# Hardware_Schematic.net
KiCad netlist of a schematic drawn in EAGLE
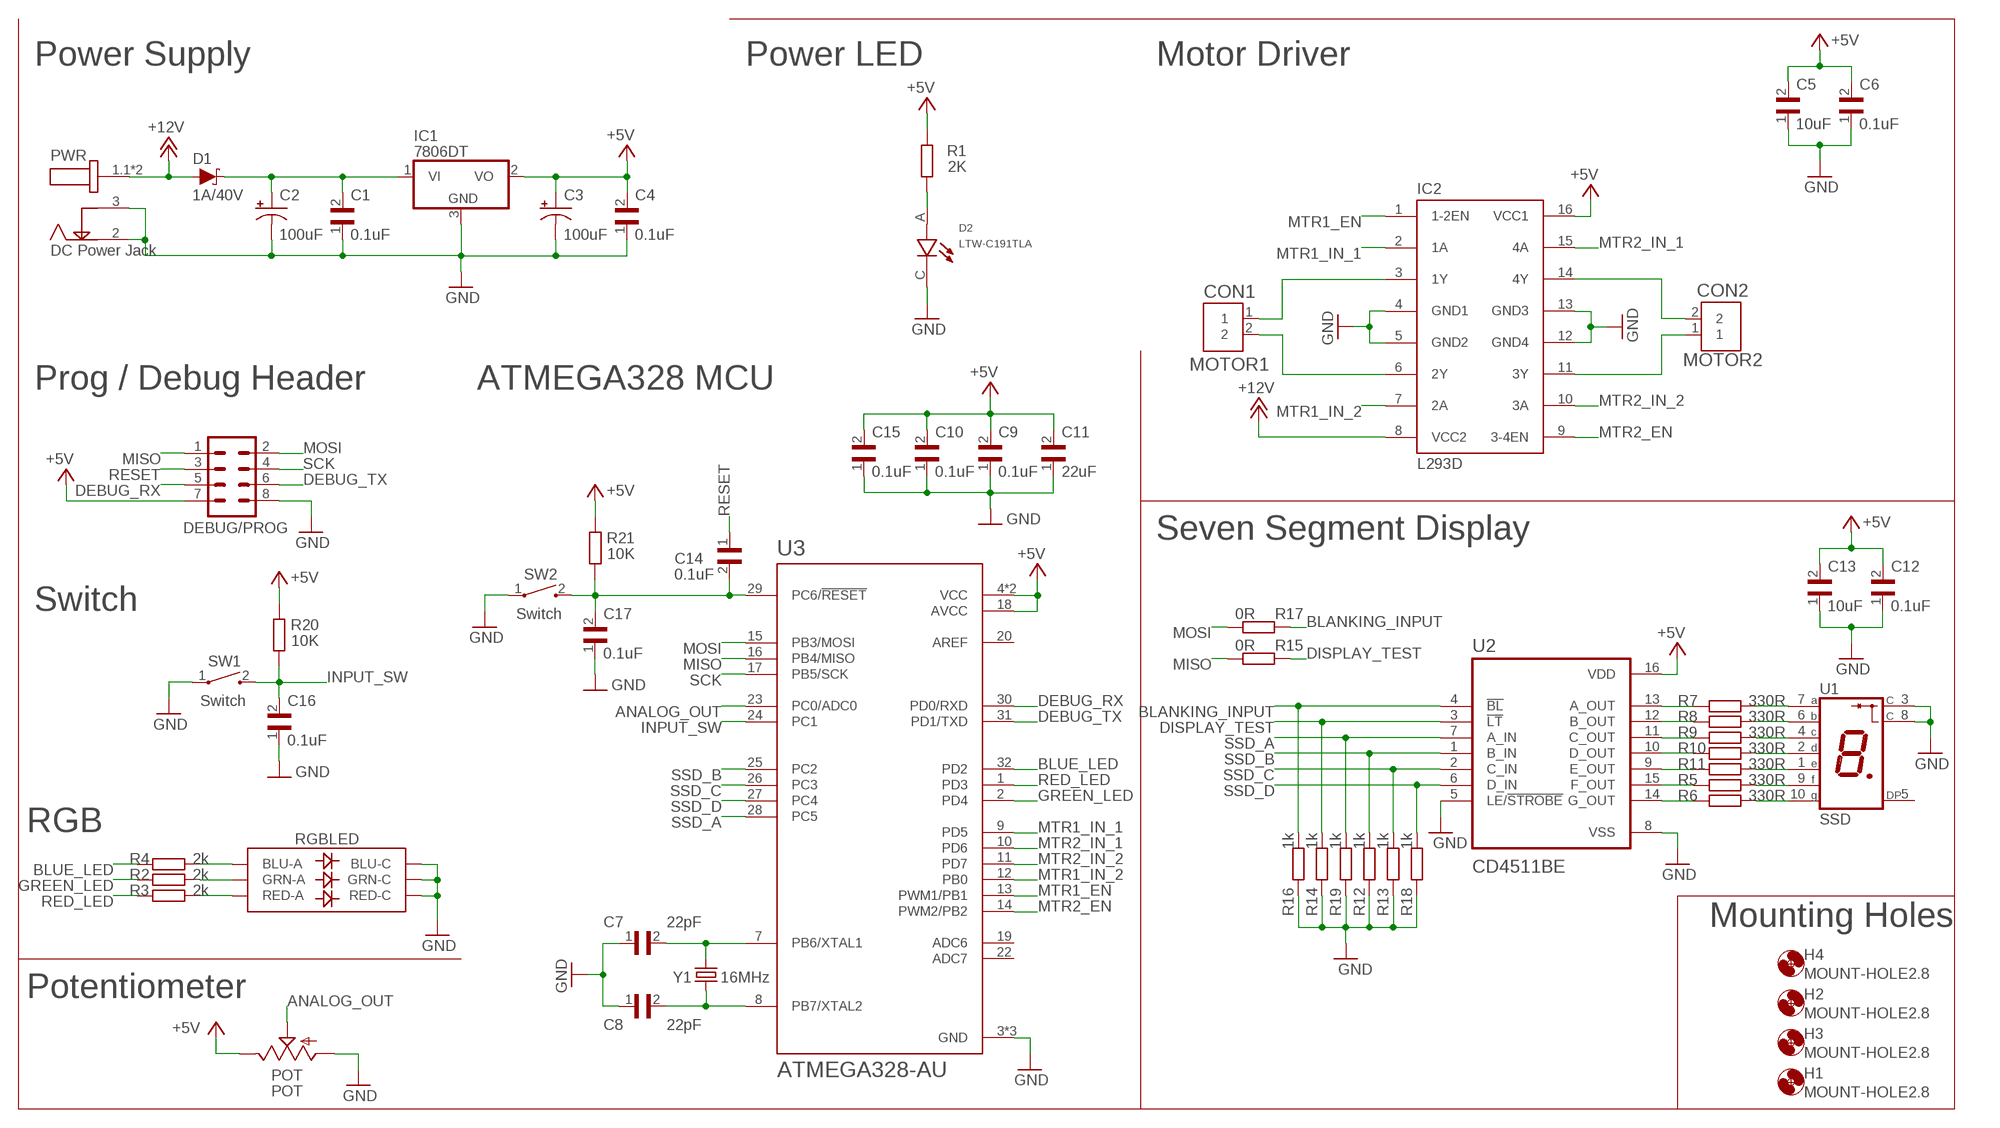
[diagram p0: schematic, sheet 1]

(export (version "E")
  (design (tool "Eeschema 10.0.6"))
  (components
    (comp (ref "C1")
      (value "0.1uF")
      (footprint "eagle-import:C0603")
      (fields (field (name "MF") "TDK") (field (name "MP") "CGA3E2X7R1H104K080AA"))
      (libsource (lib "eagle-import") (part "CAPACITOR"))
    )
    (comp (ref "C2")
      (value "100uF")
      (footprint "eagle-import:CPOL-RADIAL-2.5MM-6.5MM")
      (libsource (lib "eagle-import") (part "100UF-POLAR-RADIAL-2.5MM-25V-20%"))
    )
    (comp (ref "C3")
      (value "100uF")
      (footprint "eagle-import:CPOL-RADIAL-2.5MM-6.5MM")
      (libsource (lib "eagle-import") (part "100UF-POLAR-RADIAL-2.5MM-25V-20%"))
    )
    (comp (ref "C4")
      (value "0.1uF")
      (footprint "eagle-import:C0603")
      (fields (field (name "MF") "TDK") (field (name "MP") "CGA3E2X7R1H104K080AA"))
      (libsource (lib "eagle-import") (part "CAPACITOR"))
    )
    (comp (ref "C5")
      (value "10uF")
      (footprint "eagle-import:C0603")
      (fields (field (name "MF") "TDK") (field (name "MP") "CGA3E2X7R1H104K080AA"))
      (libsource (lib "eagle-import") (part "CAPACITOR"))
    )
    (comp (ref "C6")
      (value "0.1uF")
      (footprint "eagle-import:C0603")
      (fields (field (name "MF") "TDK") (field (name "MP") "CGA3E2X7R1H104K080AA"))
      (libsource (lib "eagle-import") (part "CAPACITOR"))
    )
    (comp (ref "C7")
      (value "22pF")
      (footprint "eagle-import:C0603")
      (fields (field (name "MF") "TDK") (field (name "MP") "CGA3E2X7R1H104K080AA"))
      (libsource (lib "eagle-import") (part "CAPACITOR"))
    )
    (comp (ref "C8")
      (value "22pF")
      (footprint "eagle-import:C0603")
      (fields (field (name "MF") "TDK") (field (name "MP") "CGA3E2X7R1H104K080AA"))
      (libsource (lib "eagle-import") (part "CAPACITOR"))
    )
    (comp (ref "C9")
      (value "0.1uF")
      (footprint "eagle-import:C0603")
      (fields (field (name "MF") "TDK") (field (name "MP") "CGA3E2X7R1H104K080AA"))
      (libsource (lib "eagle-import") (part "CAPACITOR"))
    )
    (comp (ref "C10")
      (value "0.1uF")
      (footprint "eagle-import:C0603")
      (fields (field (name "MF") "TDK") (field (name "MP") "CGA3E2X7R1H104K080AA"))
      (libsource (lib "eagle-import") (part "CAPACITOR"))
    )
    (comp (ref "C11")
      (value "22uF")
      (footprint "eagle-import:C0603")
      (fields (field (name "MF") "TDK") (field (name "MP") "CGA3E2X7R1H104K080AA"))
      (libsource (lib "eagle-import") (part "CAPACITOR"))
    )
    (comp (ref "C12")
      (value "0.1uF")
      (footprint "eagle-import:C0603")
      (fields (field (name "MF") "TDK") (field (name "MP") "CGA3E2X7R1H104K080AA"))
      (libsource (lib "eagle-import") (part "CAPACITOR"))
    )
    (comp (ref "C13")
      (value "10uF")
      (footprint "eagle-import:C0603")
      (fields (field (name "MF") "TDK") (field (name "MP") "CGA3E2X7R1H104K080AA"))
      (libsource (lib "eagle-import") (part "CAPACITOR"))
    )
    (comp (ref "C14")
      (value "0.1uF")
      (footprint "eagle-import:C0603")
      (fields (field (name "MF") "TDK") (field (name "MP") "CGA3E2X7R1H104K080AA"))
      (libsource (lib "eagle-import") (part "CAPACITOR"))
    )
    (comp (ref "C15")
      (value "0.1uF")
      (footprint "eagle-import:C0603")
      (fields (field (name "MF") "TDK") (field (name "MP") "CGA3E2X7R1H104K080AA"))
      (libsource (lib "eagle-import") (part "CAPACITOR"))
    )
    (comp (ref "C16")
      (value "0.1uF")
      (footprint "eagle-import:C0603")
      (fields (field (name "MF") "TDK") (field (name "MP") "CGA3E2X7R1H104K080AA"))
      (libsource (lib "eagle-import") (part "CAPACITOR"))
    )
    (comp (ref "C17")
      (value "0.1uF")
      (footprint "eagle-import:C0603")
      (fields (field (name "MF") "TDK") (field (name "MP") "CGA3E2X7R1H104K080AA"))
      (libsource (lib "eagle-import") (part "CAPACITOR"))
    )
    (comp (ref "CON1")
      (value "MOTOR1")
      (footprint "eagle-import:CONN_282836-2")
      (fields (field (name "COMMENT") "282836-2") (field (name "MF") "TE Connectivity"))
      (libsource (lib "eagle-import") (part "282836-2"))
    )
    (comp (ref "CON2")
      (value "MOTOR2")
      (footprint "eagle-import:CONN_282836-2")
      (fields (field (name "COMMENT") "282836-2") (field (name "MF") "TE Connectivity"))
      (libsource (lib "eagle-import") (part "282836-2"))
    )
    (comp (ref "D1")
      (value "1A/40V")
      (footprint "eagle-import:SMA-DIODE")
      (libsource (lib "eagle-import") (part "DIODE-SCHOTTKY-SS14"))
    )
    (comp (ref "D2")
      (value "LTW-C191TLA")
      (footprint "eagle-import:LEDC1608X65N")
      (fields (field (name "MF") "Lite-On"))
      (libsource (lib "eagle-import") (part "LTW-C191TLA"))
    )
    (comp (ref "DEBUG/PROG")
      (value "MA04-2")
      (footprint "eagle-import:MA04-2")
      (libsource (lib "eagle-import") (part "MA04-2"))
    )
    (comp (ref "H1")
      (value "MOUNT-HOLE2.8")
      (footprint "eagle-import:2,8")
      (libsource (lib "eagle-import") (part "MOUNT-HOLE2.8"))
    )
    (comp (ref "H2")
      (value "MOUNT-HOLE2.8")
      (footprint "eagle-import:2,8")
      (libsource (lib "eagle-import") (part "MOUNT-HOLE2.8"))
    )
    (comp (ref "H3")
      (value "MOUNT-HOLE2.8")
      (footprint "eagle-import:2,8")
      (libsource (lib "eagle-import") (part "MOUNT-HOLE2.8"))
    )
    (comp (ref "H4")
      (value "MOUNT-HOLE2.8")
      (footprint "eagle-import:2,8")
      (libsource (lib "eagle-import") (part "MOUNT-HOLE2.8"))
    )
    (comp (ref "IC1")
      (value "7806DT")
      (footprint "eagle-import:TO252")
      (libsource (lib "eagle-import") (part "78DT06"))
    )
    (comp (ref "IC2")
      (value "L293D")
      (footprint "eagle-import:DIL16")
      (libsource (lib "eagle-import") (part "L293D"))
    )
    (comp (ref "POT")
      (value "POT")
      (footprint "eagle-import:S64W")
      (libsource (lib "eagle-import") (part "TRIM_US-S64W"))
    )
    (comp (ref "PWR")
      (value "DC Power Jack")
      (footprint "eagle-import:GCT_DCJ200-05-A-XX-X_REVA")
      (fields (field (name "MF") "Global Connector Technology") (field (name "MP") "DCJ200-05-A-K1-A"))
      (libsource (lib "eagle-import") (part "DCJ200-05-A-XX-X_REVA"))
    )
    (comp (ref "R1")
      (value "2K")
      (footprint "eagle-import:R0603")
      (fields (field (name "MF") "Yageo"))
      (libsource (lib "eagle-import") (part "RESISTOR"))
    )
    (comp (ref "R2")
      (value "2k")
      (footprint "eagle-import:R0603")
      (fields (field (name "MF") "Yageo"))
      (libsource (lib "eagle-import") (part "RESISTOR"))
    )
    (comp (ref "R3")
      (value "2k")
      (footprint "eagle-import:R0603")
      (fields (field (name "MF") "Yageo"))
      (libsource (lib "eagle-import") (part "RESISTOR"))
    )
    (comp (ref "R4")
      (value "2k")
      (footprint "eagle-import:R0603")
      (fields (field (name "MF") "Yageo"))
      (libsource (lib "eagle-import") (part "RESISTOR"))
    )
    (comp (ref "R5")
      (value "330R")
      (footprint "eagle-import:R0603")
      (fields (field (name "MF") "Yageo"))
      (libsource (lib "eagle-import") (part "RESISTOR"))
    )
    (comp (ref "R6")
      (value "330R")
      (footprint "eagle-import:R0603")
      (fields (field (name "MF") "Yageo"))
      (libsource (lib "eagle-import") (part "RESISTOR"))
    )
    (comp (ref "R7")
      (value "330R")
      (footprint "eagle-import:R0603")
      (fields (field (name "MF") "Yageo"))
      (libsource (lib "eagle-import") (part "RESISTOR"))
    )
    (comp (ref "R8")
      (value "330R")
      (footprint "eagle-import:R0603")
      (fields (field (name "MF") "Yageo"))
      (libsource (lib "eagle-import") (part "RESISTOR"))
    )
    (comp (ref "R9")
      (value "330R")
      (footprint "eagle-import:R0603")
      (fields (field (name "MF") "Yageo"))
      (libsource (lib "eagle-import") (part "RESISTOR"))
    )
    (comp (ref "R10")
      (value "330R")
      (footprint "eagle-import:R0603")
      (fields (field (name "MF") "Yageo"))
      (libsource (lib "eagle-import") (part "RESISTOR"))
    )
    (comp (ref "R11")
      (value "330R")
      (footprint "eagle-import:R0603")
      (fields (field (name "MF") "Yageo"))
      (libsource (lib "eagle-import") (part "RESISTOR"))
    )
    (comp (ref "R12")
      (value "1k")
      (footprint "eagle-import:R0603")
      (fields (field (name "MF") "Yageo"))
      (libsource (lib "eagle-import") (part "RESISTOR"))
    )
    (comp (ref "R13")
      (value "1k")
      (footprint "eagle-import:R0603")
      (fields (field (name "MF") "Yageo"))
      (libsource (lib "eagle-import") (part "RESISTOR"))
    )
    (comp (ref "R14")
      (value "1k")
      (footprint "eagle-import:R0603")
      (fields (field (name "MF") "Yageo"))
      (libsource (lib "eagle-import") (part "RESISTOR"))
    )
    (comp (ref "R15")
      (value "0R")
      (footprint "eagle-import:R0603")
      (fields (field (name "MF") "Yageo"))
      (libsource (lib "eagle-import") (part "RESISTOR"))
    )
    (comp (ref "R16")
      (value "1k")
      (footprint "eagle-import:R0603")
      (fields (field (name "MF") "Yageo"))
      (libsource (lib "eagle-import") (part "RESISTOR"))
    )
    (comp (ref "R17")
      (value "0R")
      (footprint "eagle-import:R0603")
      (fields (field (name "MF") "Yageo"))
      (libsource (lib "eagle-import") (part "RESISTOR"))
    )
    (comp (ref "R18")
      (value "1k")
      (footprint "eagle-import:R0603")
      (fields (field (name "MF") "Yageo"))
      (libsource (lib "eagle-import") (part "RESISTOR"))
    )
    (comp (ref "R19")
      (value "1k")
      (footprint "eagle-import:R0603")
      (fields (field (name "MF") "Yageo"))
      (libsource (lib "eagle-import") (part "RESISTOR"))
    )
    (comp (ref "R20")
      (value "10K")
      (footprint "eagle-import:R0603")
      (fields (field (name "MF") "Yageo"))
      (libsource (lib "eagle-import") (part "RESISTOR"))
    )
    (comp (ref "R21")
      (value "10K")
      (footprint "eagle-import:R0603")
      (fields (field (name "MF") "Yageo"))
      (libsource (lib "eagle-import") (part "RESISTOR"))
    )
    (comp (ref "RGBLED")
      (value "LED-RGBNO_IC")
      (footprint "eagle-import:LED-TRICOLOR-5050")
      (libsource (lib "eagle-import") (part "LED-RGBNO_IC"))
    )
    (comp (ref "SW1")
      (value "Switch")
      (footprint "eagle-import:SW_1437566-3")
      (fields (field (name "COMMENT") "1437566-3") (field (name "MF") "TE Connectivity"))
      (libsource (lib "eagle-import") (part "1437566-3"))
    )
    (comp (ref "SW2")
      (value "Switch")
      (footprint "eagle-import:SW_1437566-3")
      (fields (field (name "COMMENT") "1437566-3") (field (name "MF") "TE Connectivity"))
      (libsource (lib "eagle-import") (part "1437566-3"))
    )
    (comp (ref "U1")
      (value "SSD")
      (footprint "eagle-import:LED_SC52-11HWA")
      (fields (field (name "MF") "Kingbright") (field (name "MP") "SC52-11HWA"))
      (libsource (lib "eagle-import") (part "SC52-11HWA"))
    )
    (comp (ref "U2")
      (value "CD4511BE")
      (footprint "eagle-import:DIP794W45P254L1969H508Q16")
      (fields (field (name "MF") "Texas Instruments"))
      (libsource (lib "eagle-import") (part "CD4511BE"))
    )
    (comp (ref "U3")
      (value "ATMEGA328-AU")
      (footprint "eagle-import:QFP80P900X900X120-32N")
      (fields (field (name "MF") "Microchip"))
      (libsource (lib "eagle-import") (part "ATMEGA328-AU"))
    )
    (comp (ref "Y1")
      (value "16MHz")
      (footprint "eagle-import:HC49US")
      (libsource (lib "eagle-import") (part "CRYSTAL-16MHZPTH-HC49US"))
    )
  )
  (nets
    (net (code "1") (name "+5V") (class "Default")
      (node (ref "C10") (pin "2") (pinfunction "2_2") (pintype "passive"))
      (node (ref "C11") (pin "2") (pinfunction "2_2") (pintype "passive"))
      (node (ref "C12") (pin "2") (pinfunction "2_2") (pintype "passive"))
      (node (ref "C13") (pin "2") (pinfunction "2_2") (pintype "passive"))
      (node (ref "C15") (pin "2") (pinfunction "2_2") (pintype "passive"))
      (node (ref "C3") (pin "1") (pinfunction "+_1") (pintype "passive"))
      (node (ref "C4") (pin "2") (pinfunction "2_2") (pintype "passive"))
      (node (ref "C5") (pin "2") (pinfunction "2_2") (pintype "passive"))
      (node (ref "C6") (pin "2") (pinfunction "2_2") (pintype "passive"))
      (node (ref "C9") (pin "2") (pinfunction "2_2") (pintype "passive"))
      (node (ref "DEBUG/PROG") (pin "7") (pinfunction "7_7") (pintype "passive"))
      (node (ref "IC1") (pin "2") (pinfunction "VO_2") (pintype "passive"))
      (node (ref "IC2") (pin "16") (pinfunction "VCC1_16") (pintype "power_in"))
      (node (ref "POT") (pin "E") (pinfunction "E_E") (pintype "passive"))
      (node (ref "R1") (pin "2") (pinfunction "2_2") (pintype "passive"))
      (node (ref "R20") (pin "2") (pinfunction "2_2") (pintype "passive"))
      (node (ref "R21") (pin "2") (pinfunction "2_2") (pintype "passive"))
      (node (ref "U2") (pin "16") (pinfunction "VDD_16") (pintype "power_in"))
      (node (ref "U3") (pin "18") (pinfunction "AVCC_18") (pintype "power_in"))
      (node (ref "U3") (pin "4") (pinfunction "VCC_4") (pintype "power_in"))
      (node (ref "U3") (pin "6") (pinfunction "VCC_6") (pintype "power_in"))
    )
    (net (code "2") (name "+12V") (class "Default")
      (node (ref "D1") (pin "A") (pinfunction "A_A") (pintype "passive"))
      (node (ref "IC2") (pin "8") (pinfunction "VCC2_8") (pintype "power_in"))
      (node (ref "PWR") (pin "1.1") (pinfunction "1_1.1") (pintype "passive"))
      (node (ref "PWR") (pin "1.2") (pinfunction "1_1.2") (pintype "passive"))
    )
    (net (code "3") (name "/ANALOG_OUT") (class "Default")
      (node (ref "POT") (pin "S") (pinfunction "S_S") (pintype "passive"))
      (node (ref "U3") (pin "23") (pinfunction "PC0/ADC0_23") (pintype "bidirectional"))
    )
    (net (code "4") (name "/BLANKING_INPUT") (class "Default")
      (node (ref "R16") (pin "2") (pinfunction "2_2") (pintype "passive"))
      (node (ref "R17") (pin "1") (pinfunction "1_1") (pintype "passive"))
      (node (ref "U2") (pin "4") (pinfunction "~{BL}_4") (pintype "input"))
    )
    (net (code "5") (name "/BLUE_LED") (class "Default")
      (node (ref "R4") (pin "1") (pinfunction "1_1") (pintype "passive"))
      (node (ref "U3") (pin "32") (pinfunction "PD2_32") (pintype "bidirectional"))
    )
    (net (code "6") (name "/DEBUG_RX") (class "Default")
      (node (ref "DEBUG/PROG") (pin "5") (pinfunction "5_5") (pintype "passive"))
      (node (ref "U3") (pin "30") (pinfunction "PD0/RXD_30") (pintype "bidirectional"))
    )
    (net (code "7") (name "/DEBUG_TX") (class "Default")
      (node (ref "DEBUG/PROG") (pin "6") (pinfunction "6_6") (pintype "passive"))
      (node (ref "U3") (pin "31") (pinfunction "PD1/TXD_31") (pintype "bidirectional"))
    )
    (net (code "8") (name "/DISPLAY_TEST") (class "Default")
      (node (ref "R14") (pin "2") (pinfunction "2_2") (pintype "passive"))
      (node (ref "R15") (pin "1") (pinfunction "1_1") (pintype "passive"))
      (node (ref "U2") (pin "3") (pinfunction "~{LT}_3") (pintype "input"))
    )
    (net (code "9") (name "/GREEN_LED") (class "Default")
      (node (ref "R2") (pin "1") (pinfunction "1_1") (pintype "passive"))
      (node (ref "U3") (pin "2") (pinfunction "PD4_2") (pintype "bidirectional"))
    )
    (net (code "10") (name "/INPUT_SW") (class "Default")
      (node (ref "C16") (pin "2") (pinfunction "2_2") (pintype "passive"))
      (node (ref "R20") (pin "1") (pinfunction "1_1") (pintype "passive"))
      (node (ref "SW1") (pin "2") (pinfunction "2_2") (pintype "passive"))
      (node (ref "U3") (pin "24") (pinfunction "PC1_24") (pintype "bidirectional"))
    )
    (net (code "11") (name "/MISO") (class "Default")
      (node (ref "DEBUG/PROG") (pin "1") (pinfunction "1_1") (pintype "passive"))
      (node (ref "R15") (pin "2") (pinfunction "2_2") (pintype "passive"))
      (node (ref "U3") (pin "16") (pinfunction "PB4/MISO_16") (pintype "bidirectional"))
    )
    (net (code "12") (name "/MOSI") (class "Default")
      (node (ref "DEBUG/PROG") (pin "2") (pinfunction "2_2") (pintype "passive"))
      (node (ref "R17") (pin "2") (pinfunction "2_2") (pintype "passive"))
      (node (ref "U3") (pin "15") (pinfunction "PB3/MOSI_15") (pintype "bidirectional"))
    )
    (net (code "13") (name "/MTR1_EN") (class "Default")
      (node (ref "IC2") (pin "1") (pinfunction "1-2EN_1") (pintype "input"))
      (node (ref "U3") (pin "13") (pinfunction "PWM1/PB1_13") (pintype "bidirectional"))
    )
    (net (code "14") (name "/MTR1_IN_1") (class "Default")
      (node (ref "IC2") (pin "2") (pinfunction "1A_2") (pintype "input"))
      (node (ref "U3") (pin "9") (pinfunction "PD5_9") (pintype "bidirectional"))
    )
    (net (code "15") (name "/MTR1_IN_2") (class "Default")
      (node (ref "IC2") (pin "7") (pinfunction "2A_7") (pintype "input"))
      (node (ref "U3") (pin "12") (pinfunction "PB0_12") (pintype "bidirectional"))
    )
    (net (code "16") (name "/MTR2_EN") (class "Default")
      (node (ref "IC2") (pin "9") (pinfunction "3-4EN_9") (pintype "input"))
      (node (ref "U3") (pin "14") (pinfunction "PWM2/PB2_14") (pintype "bidirectional"))
    )
    (net (code "17") (name "/MTR2_IN_1") (class "Default")
      (node (ref "IC2") (pin "15") (pinfunction "4A_15") (pintype "input"))
      (node (ref "U3") (pin "10") (pinfunction "PD6_10") (pintype "bidirectional"))
    )
    (net (code "18") (name "/MTR2_IN_2") (class "Default")
      (node (ref "IC2") (pin "10") (pinfunction "3A_10") (pintype "input"))
      (node (ref "U3") (pin "11") (pinfunction "PD7_11") (pintype "bidirectional"))
    )
    (net (code "19") (name "/RED_LED") (class "Default")
      (node (ref "R3") (pin "1") (pinfunction "1_1") (pintype "passive"))
      (node (ref "U3") (pin "1") (pinfunction "PD3_1") (pintype "bidirectional"))
    )
    (net (code "20") (name "/RESET") (class "Default")
      (node (ref "C14") (pin "1") (pinfunction "1_1") (pintype "passive"))
      (node (ref "DEBUG/PROG") (pin "3") (pinfunction "3_3") (pintype "passive"))
    )
    (net (code "21") (name "/SCK") (class "Default")
      (node (ref "DEBUG/PROG") (pin "4") (pinfunction "4_4") (pintype "passive"))
      (node (ref "U3") (pin "17") (pinfunction "PB5/SCK_17") (pintype "bidirectional"))
    )
    (net (code "22") (name "/SSD_A") (class "Default")
      (node (ref "R19") (pin "2") (pinfunction "2_2") (pintype "passive"))
      (node (ref "U2") (pin "7") (pinfunction "A_IN_7") (pintype "input"))
      (node (ref "U3") (pin "28") (pinfunction "PC5_28") (pintype "bidirectional"))
    )
    (net (code "23") (name "/SSD_B") (class "Default")
      (node (ref "R12") (pin "2") (pinfunction "2_2") (pintype "passive"))
      (node (ref "U2") (pin "1") (pinfunction "B_IN_1") (pintype "input"))
      (node (ref "U3") (pin "25") (pinfunction "PC2_25") (pintype "bidirectional"))
    )
    (net (code "24") (name "/SSD_C") (class "Default")
      (node (ref "R13") (pin "2") (pinfunction "2_2") (pintype "passive"))
      (node (ref "U2") (pin "2") (pinfunction "C_IN_2") (pintype "input"))
      (node (ref "U3") (pin "26") (pinfunction "PC3_26") (pintype "bidirectional"))
    )
    (net (code "25") (name "/SSD_D") (class "Default")
      (node (ref "R18") (pin "2") (pinfunction "2_2") (pintype "passive"))
      (node (ref "U2") (pin "6") (pinfunction "D_IN_6") (pintype "input"))
      (node (ref "U3") (pin "27") (pinfunction "PC4_27") (pintype "bidirectional"))
    )
    (net (code "26") (name "GND") (class "Default")
      (node (ref "C1") (pin "1") (pinfunction "1_1") (pintype "passive"))
      (node (ref "C10") (pin "1") (pinfunction "1_1") (pintype "passive"))
      (node (ref "C11") (pin "1") (pinfunction "1_1") (pintype "passive"))
      (node (ref "C12") (pin "1") (pinfunction "1_1") (pintype "passive"))
      (node (ref "C13") (pin "1") (pinfunction "1_1") (pintype "passive"))
      (node (ref "C15") (pin "1") (pinfunction "1_1") (pintype "passive"))
      (node (ref "C16") (pin "1") (pinfunction "1_1") (pintype "passive"))
      (node (ref "C17") (pin "1") (pinfunction "1_1") (pintype "passive"))
      (node (ref "C2") (pin "2") (pinfunction "-_2") (pintype "passive"))
      (node (ref "C3") (pin "2") (pinfunction "-_2") (pintype "passive"))
      (node (ref "C4") (pin "1") (pinfunction "1_1") (pintype "passive"))
      (node (ref "C5") (pin "1") (pinfunction "1_1") (pintype "passive"))
      (node (ref "C6") (pin "1") (pinfunction "1_1") (pintype "passive"))
      (node (ref "C7") (pin "1") (pinfunction "1_1") (pintype "passive"))
      (node (ref "C8") (pin "1") (pinfunction "1_1") (pintype "passive"))
      (node (ref "C9") (pin "1") (pinfunction "1_1") (pintype "passive"))
      (node (ref "D2") (pin "C") (pinfunction "C_C") (pintype "passive"))
      (node (ref "DEBUG/PROG") (pin "8") (pinfunction "8_8") (pintype "passive"))
      (node (ref "IC1") (pin "3") (pinfunction "GND_3") (pintype "passive"))
      (node (ref "IC2") (pin "12") (pinfunction "GND4_12") (pintype "power_in"))
      (node (ref "IC2") (pin "13") (pinfunction "GND3_13") (pintype "power_in"))
      (node (ref "IC2") (pin "4") (pinfunction "GND1_4") (pintype "power_in"))
      (node (ref "IC2") (pin "5") (pinfunction "GND2_5") (pintype "power_in"))
      (node (ref "POT") (pin "A") (pinfunction "A_A") (pintype "passive"))
      (node (ref "PWR") (pin "2") (pinfunction "2_2") (pintype "passive"))
      (node (ref "PWR") (pin "3") (pinfunction "3_3") (pintype "passive"))
      (node (ref "R12") (pin "1") (pinfunction "1_1") (pintype "passive"))
      (node (ref "R13") (pin "1") (pinfunction "1_1") (pintype "passive"))
      (node (ref "R14") (pin "1") (pinfunction "1_1") (pintype "passive"))
      (node (ref "R16") (pin "1") (pinfunction "1_1") (pintype "passive"))
      (node (ref "R18") (pin "1") (pinfunction "1_1") (pintype "passive"))
      (node (ref "R19") (pin "1") (pinfunction "1_1") (pintype "passive"))
      (node (ref "RGBLED") (pin "4") (pinfunction "BLU-C_4") (pintype "bidirectional"))
      (node (ref "RGBLED") (pin "5") (pinfunction "RED-C_5") (pintype "bidirectional"))
      (node (ref "RGBLED") (pin "6") (pinfunction "GRN-C_6") (pintype "bidirectional"))
      (node (ref "SW1") (pin "1") (pinfunction "1_1") (pintype "passive"))
      (node (ref "SW2") (pin "1") (pinfunction "1_1") (pintype "passive"))
      (node (ref "U1") (pin "3") (pinfunction "C_3") (pintype "passive"))
      (node (ref "U1") (pin "8") (pinfunction "C_8") (pintype "passive"))
      (node (ref "U2") (pin "5") (pinfunction "LE/~{STROBE}_5") (pintype "input"))
      (node (ref "U2") (pin "8") (pinfunction "VSS_8") (pintype "power_in"))
      (node (ref "U3") (pin "21") (pinfunction "GND_21") (pintype "power_in"))
      (node (ref "U3") (pin "3") (pinfunction "GND_3") (pintype "power_in"))
      (node (ref "U3") (pin "5") (pinfunction "GND_5") (pintype "power_in"))
    )
    (net (code "27") (name "Net-(C2-+)") (class "Default")
      (node (ref "C1") (pin "2") (pinfunction "2_2") (pintype "passive"))
      (node (ref "C2") (pin "1") (pinfunction "+_1") (pintype "passive"))
      (node (ref "D1") (pin "C") (pinfunction "C_C") (pintype "passive"))
      (node (ref "IC1") (pin "1") (pinfunction "VI_1") (pintype "input"))
    )
    (net (code "28") (name "Net-(D2-PadA)") (class "Default")
      (node (ref "D2") (pin "A") (pinfunction "A_A") (pintype "passive"))
      (node (ref "R1") (pin "1") (pinfunction "1_1") (pintype "passive"))
    )
    (net (code "29") (name "Net-(IC2-1Y)") (class "Default")
      (node (ref "CON1") (pin "1") (pinfunction "1_1") (pintype "passive"))
      (node (ref "IC2") (pin "3") (pinfunction "1Y_3") (pintype "output"))
    )
    (net (code "30") (name "Net-(IC2-2Y)") (class "Default")
      (node (ref "CON1") (pin "2") (pinfunction "2_2") (pintype "passive"))
      (node (ref "IC2") (pin "6") (pinfunction "2Y_6") (pintype "output"))
    )
    (net (code "31") (name "Net-(IC2-3Y)") (class "Default")
      (node (ref "CON2") (pin "1") (pinfunction "1_1") (pintype "passive"))
      (node (ref "IC2") (pin "11") (pinfunction "3Y_11") (pintype "output"))
    )
    (net (code "32") (name "Net-(IC2-4Y)") (class "Default")
      (node (ref "CON2") (pin "2") (pinfunction "2_2") (pintype "passive"))
      (node (ref "IC2") (pin "14") (pinfunction "4Y_14") (pintype "output"))
    )
    (net (code "33") (name "Net-(R9-Pad2)") (class "Default")
      (node (ref "R9") (pin "2") (pinfunction "2_2") (pintype "passive"))
      (node (ref "U1") (pin "4") (pinfunction "C_4") (pintype "passive"))
    )
    (net (code "34") (name "Net-(RGBLED-BLU-A)") (class "Default")
      (node (ref "R4") (pin "2") (pinfunction "2_2") (pintype "passive"))
      (node (ref "RGBLED") (pin "3") (pinfunction "BLU-A_3") (pintype "bidirectional"))
    )
    (net (code "35") (name "Net-(RGBLED-GRN-A)") (class "Default")
      (node (ref "R2") (pin "2") (pinfunction "2_2") (pintype "passive"))
      (node (ref "RGBLED") (pin "1") (pinfunction "GRN-A_1") (pintype "bidirectional"))
    )
    (net (code "36") (name "Net-(RGBLED-RED-A)") (class "Default")
      (node (ref "R3") (pin "2") (pinfunction "2_2") (pintype "passive"))
      (node (ref "RGBLED") (pin "2") (pinfunction "RED-A_2") (pintype "bidirectional"))
    )
    (net (code "37") (name "Net-(U1-A)") (class "Default")
      (node (ref "R7") (pin "2") (pinfunction "2_2") (pintype "passive"))
      (node (ref "U1") (pin "7") (pinfunction "A_7") (pintype "passive"))
    )
    (net (code "38") (name "Net-(U1-B)") (class "Default")
      (node (ref "R8") (pin "2") (pinfunction "2_2") (pintype "passive"))
      (node (ref "U1") (pin "6") (pinfunction "B_6") (pintype "passive"))
    )
    (net (code "39") (name "Net-(U1-D)") (class "Default")
      (node (ref "R10") (pin "2") (pinfunction "2_2") (pintype "passive"))
      (node (ref "U1") (pin "2") (pinfunction "D_2") (pintype "passive"))
    )
    (net (code "40") (name "Net-(U1-E)") (class "Default")
      (node (ref "R11") (pin "2") (pinfunction "2_2") (pintype "passive"))
      (node (ref "U1") (pin "1") (pinfunction "E_1") (pintype "passive"))
    )
    (net (code "41") (name "Net-(U1-F)") (class "Default")
      (node (ref "R5") (pin "2") (pinfunction "2_2") (pintype "passive"))
      (node (ref "U1") (pin "9") (pinfunction "F_9") (pintype "passive"))
    )
    (net (code "42") (name "Net-(U1-G)") (class "Default")
      (node (ref "R6") (pin "2") (pinfunction "2_2") (pintype "passive"))
      (node (ref "U1") (pin "10") (pinfunction "G_10") (pintype "passive"))
    )
    (net (code "43") (name "Net-(U2-A_OUT)") (class "Default")
      (node (ref "R7") (pin "1") (pinfunction "1_1") (pintype "passive"))
      (node (ref "U2") (pin "13") (pinfunction "A_OUT_13") (pintype "output"))
    )
    (net (code "44") (name "Net-(U2-B_OUT)") (class "Default")
      (node (ref "R8") (pin "1") (pinfunction "1_1") (pintype "passive"))
      (node (ref "U2") (pin "12") (pinfunction "B_OUT_12") (pintype "output"))
    )
    (net (code "45") (name "Net-(U2-C_OUT)") (class "Default")
      (node (ref "R9") (pin "1") (pinfunction "1_1") (pintype "passive"))
      (node (ref "U2") (pin "11") (pinfunction "C_OUT_11") (pintype "output"))
    )
    (net (code "46") (name "Net-(U2-D_OUT)") (class "Default")
      (node (ref "R10") (pin "1") (pinfunction "1_1") (pintype "passive"))
      (node (ref "U2") (pin "10") (pinfunction "D_OUT_10") (pintype "output"))
    )
    (net (code "47") (name "Net-(U2-E_OUT)") (class "Default")
      (node (ref "R11") (pin "1") (pinfunction "1_1") (pintype "passive"))
      (node (ref "U2") (pin "9") (pinfunction "E_OUT_9") (pintype "output"))
    )
    (net (code "48") (name "Net-(U2-F_OUT)") (class "Default")
      (node (ref "R5") (pin "1") (pinfunction "1_1") (pintype "passive"))
      (node (ref "U2") (pin "15") (pinfunction "F_OUT_15") (pintype "output"))
    )
    (net (code "49") (name "Net-(U2-G_OUT)") (class "Default")
      (node (ref "R6") (pin "1") (pinfunction "1_1") (pintype "passive"))
      (node (ref "U2") (pin "14") (pinfunction "G_OUT_14") (pintype "output"))
    )
    (net (code "50") (name "Net-(U3-PB6{slash}XTAL1)") (class "Default")
      (node (ref "C7") (pin "2") (pinfunction "2_2") (pintype "passive"))
      (node (ref "U3") (pin "7") (pinfunction "PB6/XTAL1_7") (pintype "bidirectional"))
      (node (ref "Y1") (pin "2") (pinfunction "2_2") (pintype "passive"))
    )
    (net (code "51") (name "Net-(U3-PB7{slash}XTAL2)") (class "Default")
      (node (ref "C8") (pin "2") (pinfunction "2_2") (pintype "passive"))
      (node (ref "U3") (pin "8") (pinfunction "PB7/XTAL2_8") (pintype "bidirectional"))
      (node (ref "Y1") (pin "1") (pinfunction "1_1") (pintype "passive"))
    )
    (net (code "52") (name "Net-(U3-PC6{slash}~{RESET})") (class "Default")
      (node (ref "C14") (pin "2") (pinfunction "2_2") (pintype "passive"))
      (node (ref "C17") (pin "2") (pinfunction "2_2") (pintype "passive"))
      (node (ref "R21") (pin "1") (pinfunction "1_1") (pintype "passive"))
      (node (ref "SW2") (pin "2") (pinfunction "2_2") (pintype "passive"))
      (node (ref "U3") (pin "29") (pinfunction "PC6/~{RESET}_29") (pintype "bidirectional"))
    )
    (net (code "53") (name "unconnected-(U1-DP-Pad5)") (class "Default")
      (node (ref "U1") (pin "5") (pinfunction "DP_5") (pintype "passive"))
    )
    (net (code "54") (name "unconnected-(U3-ADC6-Pad19)") (class "Default")
      (node (ref "U3") (pin "19") (pinfunction "ADC6_19") (pintype "bidirectional"))
    )
    (net (code "55") (name "unconnected-(U3-ADC7-Pad22)") (class "Default")
      (node (ref "U3") (pin "22") (pinfunction "ADC7_22") (pintype "bidirectional"))
    )
    (net (code "56") (name "unconnected-(U3-AREF-Pad20)") (class "Default")
      (node (ref "U3") (pin "20") (pinfunction "AREF_20") (pintype "input"))
    )
  )
)
